# Buck-Boost_1.net
KiCad netlist of a schematic drawn in EasyEDA Pro
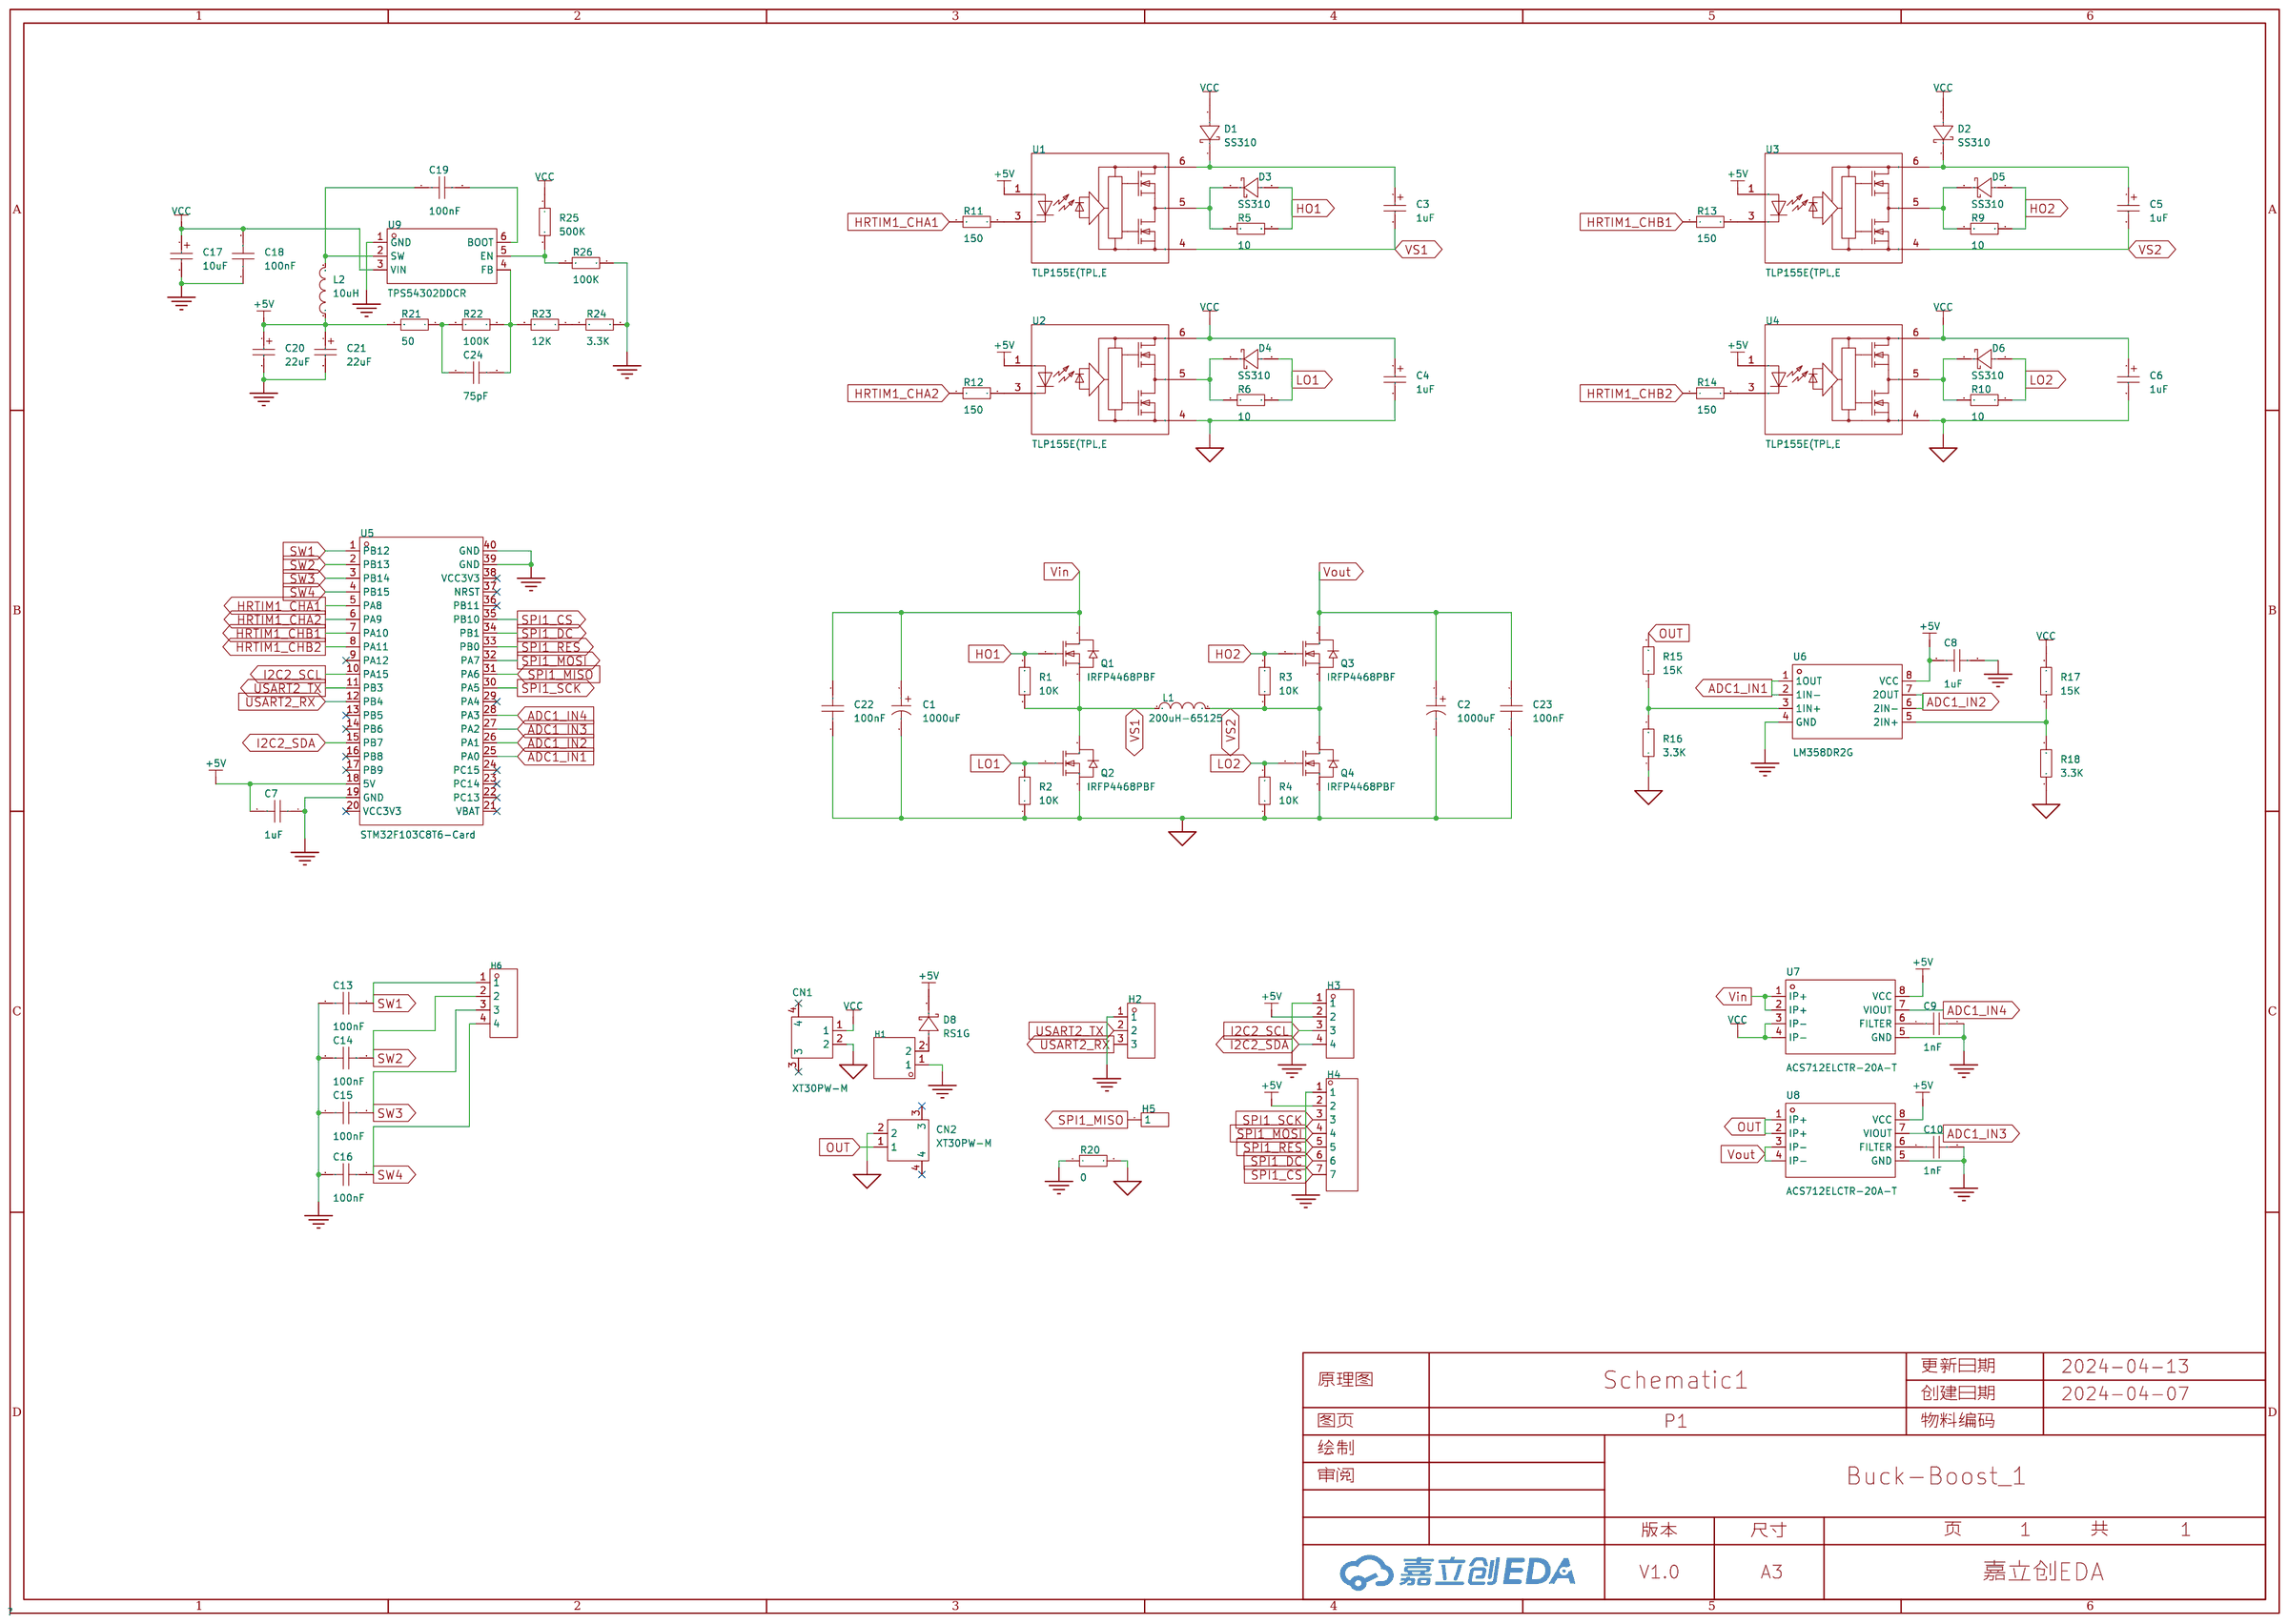
[diagram p0: schematic sheet]

(export (version "E")
  (design (tool "Eeschema 10.0.6"))
  (components
    (comp (ref "C1")
      (value "1000uF")
      (footprint "easyedapro:CAP-TH_BD16.0-P7.50-D1.5-FD")
      (description "容值:470uF;精度:±20%;额定电压:120V;纹波电流:-;等效串联电阻:-;")
      (fields (field (name "Manufacturer Part") "KF102M050I250A") (field (name "Manufacturer") "CapXon(丰宾)"))
      (libsource (lib "easyedapro") (part "ERS2BM471L35OT"))
    )
    (comp (ref "C2")
      (value "1000uF")
      (footprint "easyedapro:CAP-TH_BD16.0-P7.50-D1.5-FD")
      (description "容值:470uF;精度:±20%;额定电压:120V;纹波电流:-;等效串联电阻:-;")
      (fields (field (name "Manufacturer Part") "KF102M050I250A") (field (name "Manufacturer") "CapXon(丰宾)"))
      (libsource (lib "easyedapro") (part "ERS2BM471L35OT"))
    )
    (comp (ref "C3")
      (value "1uF")
      (footprint "easyedapro:CASE-A_3216")
      (description "容值:1uF;精度:±10%;额定电压:35V;等效串联电阻:7.5Ω@100kHz;")
      (fields (field (name "Manufacturer Part") "TAJA105K035RNJ") (field (name "Manufacturer") "Kyocera AVX"))
      (libsource (lib "easyedapro") (part "TAJA105K035RNJ"))
    )
    (comp (ref "C4")
      (value "1uF")
      (footprint "easyedapro:CASE-A_3216")
      (description "容值:1uF;精度:±10%;额定电压:35V;等效串联电阻:7.5Ω@100kHz;")
      (fields (field (name "Manufacturer Part") "TAJA105K035RNJ") (field (name "Manufacturer") "Kyocera AVX"))
      (libsource (lib "easyedapro") (part "TAJA105K035RNJ"))
    )
    (comp (ref "C5")
      (value "1uF")
      (footprint "easyedapro:CASE-A_3216")
      (description "容值:1uF;精度:±10%;额定电压:35V;等效串联电阻:7.5Ω@100kHz;")
      (fields (field (name "Manufacturer Part") "TAJA105K035RNJ") (field (name "Manufacturer") "Kyocera AVX"))
      (libsource (lib "easyedapro") (part "TAJA105K035RNJ"))
    )
    (comp (ref "C6")
      (value "1uF")
      (footprint "easyedapro:CASE-A_3216")
      (description "容值:1uF;精度:±10%;额定电压:35V;等效串联电阻:7.5Ω@100kHz;")
      (fields (field (name "Manufacturer Part") "TAJA105K035RNJ") (field (name "Manufacturer") "Kyocera AVX"))
      (libsource (lib "easyedapro") (part "TAJA105K035RNJ"))
    )
    (comp (ref "C7")
      (value "1uF")
      (footprint "easyedapro:C0805")
      (libsource (lib "easyedapro") (part "CapAcitance"))
    )
    (comp (ref "C8")
      (value "1uF")
      (footprint "easyedapro:C0805")
      (libsource (lib "easyedapro") (part "CapAcitance"))
    )
    (comp (ref "C9")
      (value "1nF")
      (footprint "easyedapro:C0805")
      (libsource (lib "easyedapro") (part "CapAcitance"))
    )
    (comp (ref "C10")
      (value "1nF")
      (footprint "easyedapro:C0805")
      (libsource (lib "easyedapro") (part "CapAcitance"))
    )
    (comp (ref "C13")
      (value "100nF")
      (footprint "easyedapro:C0805")
      (libsource (lib "easyedapro") (part "CapAcitance"))
    )
    (comp (ref "C14")
      (value "100nF")
      (footprint "easyedapro:C0805")
      (libsource (lib "easyedapro") (part "CapAcitance"))
    )
    (comp (ref "C15")
      (value "100nF")
      (footprint "easyedapro:C0805")
      (libsource (lib "easyedapro") (part "CapAcitance"))
    )
    (comp (ref "C16")
      (value "100nF")
      (footprint "easyedapro:C0805")
      (libsource (lib "easyedapro") (part "CapAcitance"))
    )
    (comp (ref "C17")
      (value "10uF")
      (footprint "easyedapro:CAP-SMD_L3.5-W2.8-R-RD")
      (description "容值:10uF;精度:±10%;额定电压:25V;等效串联电阻:2.5Ω@100kHz;")
      (fields (field (name "Manufacturer Part") "TAJB106K025RNJ") (field (name "Manufacturer") "Kyocera AVX"))
      (libsource (lib "easyedapro") (part "TAJB106K025RNJ"))
    )
    (comp (ref "C18")
      (value "100nF")
      (footprint "easyedapro:C0805")
      (libsource (lib "easyedapro") (part "CapAcitance"))
    )
    (comp (ref "C19")
      (value "100nF")
      (footprint "easyedapro:C0805")
      (libsource (lib "easyedapro") (part "CapAcitance"))
    )
    (comp (ref "C20")
      (value "22uF")
      (footprint "easyedapro:CASE-B_3528")
      (description "容值:22uF;精度:±10%;额定电压:16V;等效串联电阻:2.3Ω@100kHz;")
      (fields (field (name "Manufacturer Part") "TAJB226K016RNJ") (field (name "Manufacturer") "Kyocera AVX"))
      (libsource (lib "easyedapro") (part "TAJB226K016RNJ"))
    )
    (comp (ref "C21")
      (value "22uF")
      (footprint "easyedapro:CASE-B_3528")
      (description "容值:22uF;精度:±10%;额定电压:16V;等效串联电阻:2.3Ω@100kHz;")
      (fields (field (name "Manufacturer Part") "TAJB226K016RNJ") (field (name "Manufacturer") "Kyocera AVX"))
      (libsource (lib "easyedapro") (part "TAJB226K016RNJ"))
    )
    (comp (ref "C22")
      (value "100nF")
      (footprint "easyedapro:C0805")
      (libsource (lib "easyedapro") (part "CapAcitance"))
    )
    (comp (ref "C23")
      (value "100nF")
      (footprint "easyedapro:C0805")
      (libsource (lib "easyedapro") (part "CapAcitance"))
    )
    (comp (ref "C24")
      (value "75pF")
      (footprint "easyedapro:C0805")
      (libsource (lib "easyedapro") (part "CapAcitance"))
    )
    (comp (ref "CN1")
      (value "XT30PW-M")
      (footprint "easyedapro:CONN-TH_XT30PW-M")
      (description "类别:-;类型1:-;")
      (fields (field (name "Manufacturer") "AMASS(艾迈斯)"))
      (libsource (lib "easyedapro") (part "XT30PW-M"))
    )
    (comp (ref "CN2")
      (value "XT30PW-M")
      (footprint "easyedapro:CONN-TH_XT30PW-M")
      (description "类别:-;类型1:-;")
      (fields (field (name "Manufacturer") "AMASS(艾迈斯)"))
      (libsource (lib "easyedapro") (part "XT30PW-M"))
    )
    (comp (ref "D1")
      (value "SS310")
      (footprint "easyedapro:SMC_L6.9-W5.9-LS7.9-RD")
      (fields (field (name "Manufacturer") "MDD"))
      (libsource (lib "easyedapro") (part "SS56_C5161914"))
    )
    (comp (ref "D2")
      (value "SS310")
      (footprint "easyedapro:SMC_L6.9-W5.9-LS7.9-RD")
      (fields (field (name "Manufacturer") "MDD"))
      (libsource (lib "easyedapro") (part "SS56_C5161914"))
    )
    (comp (ref "D3")
      (value "SS310")
      (footprint "easyedapro:SMC_L6.9-W5.9-LS7.9-RD")
      (fields (field (name "Manufacturer") "MDD"))
      (libsource (lib "easyedapro") (part "SS56_C5161914"))
    )
    (comp (ref "D4")
      (value "SS310")
      (footprint "easyedapro:SMC_L6.9-W5.9-LS7.9-RD")
      (fields (field (name "Manufacturer") "MDD"))
      (libsource (lib "easyedapro") (part "SS56_C5161914"))
    )
    (comp (ref "D5")
      (value "SS310")
      (footprint "easyedapro:SMC_L6.9-W5.9-LS7.9-RD")
      (fields (field (name "Manufacturer") "MDD"))
      (libsource (lib "easyedapro") (part "SS56_C5161914"))
    )
    (comp (ref "D6")
      (value "SS310")
      (footprint "easyedapro:SMC_L6.9-W5.9-LS7.9-RD")
      (fields (field (name "Manufacturer") "MDD"))
      (libsource (lib "easyedapro") (part "SS56_C5161914"))
    )
    (comp (ref "D8")
      (value "RS1G")
      (footprint "easyedapro:SMC_L6.9-W5.9-LS7.9-RD")
      (fields (field (name "Manufacturer") "宏迦橙"))
      (libsource (lib "easyedapro") (part "SS56_C5161914"))
    )
    (comp (ref "H1")
      (value "~")
      (footprint "easyedapro:HDR-TH_2P-P2.54-V-M-1")
      (libsource (lib "easyedapro") (part "210S-1*2P L=11.6MMGold-plated black"))
    )
    (comp (ref "H2")
      (value "~")
      (footprint "easyedapro:HDR-TH_3P-P2.54-V-M")
      (libsource (lib "easyedapro") (part "PZ254V-11-03P_C2937625"))
    )
    (comp (ref "H3")
      (value "~")
      (footprint "easyedapro:HDR-TH_4P-P2.54-V-F")
      (libsource (lib "easyedapro") (part "2.54-1*4P母"))
    )
    (comp (ref "H4")
      (value "~")
      (footprint "easyedapro:HDR-TH_7P-P2.54-V-F")
      (libsource (lib "easyedapro") (part "220S-1*7P H=8.5MM Ytype Gold-plated"))
    )
    (comp (ref "H5")
      (value "~")
      (footprint "easyedapro:HDR-TH_1P-V-M_XKB_X4611WV-01I-C28D40")
      (libsource (lib "easyedapro") (part "HDR_1x1"))
    )
    (comp (ref "H6")
      (value "~")
      (footprint "easyedapro:HDR-TH_4P-P2.54-V-M")
      (libsource (lib "easyedapro") (part "PZ254V-11-04P"))
    )
    (comp (ref "L1")
      (value "200uH-65125")
      (footprint "easyedapro:IND-TH_200UH-65125")
      (libsource (lib "easyedapro") (part "200UH-65125"))
    )
    (comp (ref "L2")
      (value "10uH")
      (footprint "easyedapro:IND-SMD_L7.3-W6.8")
      (description "电感值:10uH;精度:±20%;额定电流:4.5A;饱和电流(Isat):5.5A;类型:一体成型电感;")
      (fields (field (name "Manufacturer Part") "FXL0420-100-M") (field (name "Manufacturer") "cjiang(长江微电)"))
      (libsource (lib "easyedapro") (part "FXL0630-100-M"))
    )
    (comp (ref "Q1")
      (value "IRFP4468PBF")
      (footprint "easyedapro:TO-247AC-3_L15.8-W5.0-P5.46-L")
      (fields (field (name "Manufacturer") "Infineon(英飞凌)"))
      (libsource (lib "easyedapro") (part "IRFP4468PBF"))
    )
    (comp (ref "Q2")
      (value "IRFP4468PBF")
      (footprint "easyedapro:TO-247AC-3_L15.8-W5.0-P5.46-L")
      (fields (field (name "Manufacturer") "Infineon(英飞凌)"))
      (libsource (lib "easyedapro") (part "IRFP4468PBF"))
    )
    (comp (ref "Q3")
      (value "IRFP4468PBF")
      (footprint "easyedapro:TO-247AC-3_L15.8-W5.0-P5.46-L")
      (fields (field (name "Manufacturer") "Infineon(英飞凌)"))
      (libsource (lib "easyedapro") (part "IRFP4468PBF"))
    )
    (comp (ref "Q4")
      (value "IRFP4468PBF")
      (footprint "easyedapro:TO-247AC-3_L15.8-W5.0-P5.46-L")
      (fields (field (name "Manufacturer") "Infineon(英飞凌)"))
      (libsource (lib "easyedapro") (part "IRFP4468PBF"))
    )
    (comp (ref "R1") (value "10K") (footprint "easyedapro:R0805") (libsource (lib "easyedapro") (part "电阻")))
    (comp (ref "R2") (value "10K") (footprint "easyedapro:R0805") (libsource (lib "easyedapro") (part "电阻")))
    (comp (ref "R3") (value "10K") (footprint "easyedapro:R0805") (libsource (lib "easyedapro") (part "电阻")))
    (comp (ref "R4") (value "10K") (footprint "easyedapro:R0805") (libsource (lib "easyedapro") (part "电阻")))
    (comp (ref "R5") (value "10") (footprint "easyedapro:R0805") (libsource (lib "easyedapro") (part "电阻")))
    (comp (ref "R6") (value "10") (footprint "easyedapro:R0805") (libsource (lib "easyedapro") (part "电阻")))
    (comp (ref "R9") (value "10") (footprint "easyedapro:R0805") (libsource (lib "easyedapro") (part "电阻")))
    (comp (ref "R10") (value "10") (footprint "easyedapro:R0805") (libsource (lib "easyedapro") (part "电阻")))
    (comp (ref "R11") (value "150") (footprint "easyedapro:R0805") (libsource (lib "easyedapro") (part "电阻")))
    (comp (ref "R12") (value "150") (footprint "easyedapro:R0805") (libsource (lib "easyedapro") (part "电阻")))
    (comp (ref "R13") (value "150") (footprint "easyedapro:R0805") (libsource (lib "easyedapro") (part "电阻")))
    (comp (ref "R14") (value "150") (footprint "easyedapro:R0805") (libsource (lib "easyedapro") (part "电阻")))
    (comp (ref "R15") (value "15K") (footprint "easyedapro:R0805") (libsource (lib "easyedapro") (part "电阻")))
    (comp (ref "R16")
      (value "3.3K")
      (footprint "easyedapro:R0805")
      (libsource (lib "easyedapro") (part "电阻"))
    )
    (comp (ref "R17") (value "15K") (footprint "easyedapro:R0805") (libsource (lib "easyedapro") (part "电阻")))
    (comp (ref "R18")
      (value "3.3K")
      (footprint "easyedapro:R0805")
      (libsource (lib "easyedapro") (part "电阻"))
    )
    (comp (ref "R20") (value "0") (footprint "easyedapro:R0805") (libsource (lib "easyedapro") (part "电阻")))
    (comp (ref "R21") (value "50") (footprint "easyedapro:R0805") (libsource (lib "easyedapro") (part "电阻")))
    (comp (ref "R22")
      (value "100K")
      (footprint "easyedapro:R0805")
      (libsource (lib "easyedapro") (part "电阻"))
    )
    (comp (ref "R23") (value "12K") (footprint "easyedapro:R0805") (libsource (lib "easyedapro") (part "电阻")))
    (comp (ref "R24")
      (value "3.3K")
      (footprint "easyedapro:R0805")
      (libsource (lib "easyedapro") (part "电阻"))
    )
    (comp (ref "R25")
      (value "500K")
      (footprint "easyedapro:R0805")
      (libsource (lib "easyedapro") (part "电阻"))
    )
    (comp (ref "R26")
      (value "100K")
      (footprint "easyedapro:R0805")
      (libsource (lib "easyedapro") (part "电阻"))
    )
    (comp (ref "U1")
      (value "TLP155E(TPL,E")
      (footprint "easyedapro:OPTO-SMD-5_L3.7-W4.6-P1.27-LS7.0-BR")
      (description "输入类型:DC;电源电压:10V~30V;共模瞬变抗扰度CMTI:15kV/us;传播延迟tpLH/tpHL:170ns；170ns;")
      (fields (field (name "Manufacturer") "TOSHIBA(东芝)"))
      (libsource (lib "easyedapro") (part "TLP155E(TPL,E"))
    )
    (comp (ref "U2")
      (value "TLP155E(TPL,E")
      (footprint "easyedapro:OPTO-SMD-5_L3.7-W4.6-P1.27-LS7.0-BR")
      (description "输入类型:DC;电源电压:10V~30V;共模瞬变抗扰度CMTI:15kV/us;传播延迟tpLH/tpHL:170ns；170ns;")
      (fields (field (name "Manufacturer") "TOSHIBA(东芝)"))
      (libsource (lib "easyedapro") (part "TLP155E(TPL,E"))
    )
    (comp (ref "U3")
      (value "TLP155E(TPL,E")
      (footprint "easyedapro:OPTO-SMD-5_L3.7-W4.6-P1.27-LS7.0-BR")
      (description "输入类型:DC;电源电压:10V~30V;共模瞬变抗扰度CMTI:15kV/us;传播延迟tpLH/tpHL:170ns；170ns;")
      (fields (field (name "Manufacturer") "TOSHIBA(东芝)"))
      (libsource (lib "easyedapro") (part "TLP155E(TPL,E"))
    )
    (comp (ref "U4")
      (value "TLP155E(TPL,E")
      (footprint "easyedapro:OPTO-SMD-5_L3.7-W4.6-P1.27-LS7.0-BR")
      (description "输入类型:DC;电源电压:10V~30V;共模瞬变抗扰度CMTI:15kV/us;传播延迟tpLH/tpHL:170ns；170ns;")
      (fields (field (name "Manufacturer") "TOSHIBA(东芝)"))
      (libsource (lib "easyedapro") (part "TLP155E(TPL,E"))
    )
    (comp (ref "U5")
      (value "STM32F103C8T6-Card")
      (footprint "easyedapro:CONN-TH_L53.3-W22.9_STM32F103C8T6-CARD")
      (libsource (lib "easyedapro") (part "STM32F103C8T6-CARD"))
    )
    (comp (ref "U6")
      (value "LM358DR2G")
      (footprint "easyedapro:SOIC-8_L5.0-W4.0-P1.27-LS6.0-BL")
      (description "放大器数:双路;增益带宽积(GBP):1MHz;输入偏置电流(Ib):45nA;压摆率(SR):-;带宽(-3db):-;")
      (fields (field (name "Manufacturer") "onsemi(安森美)"))
      (libsource (lib "easyedapro") (part "LM358DR2G"))
    )
    (comp (ref "U7")
      (value "ACS712ELCTR-20A-T")
      (footprint "easyedapro:SOIC-8_L4.9-W3.9-P1.27-LS6.0-BL")
      (description "电流测量范围:20A;灵敏度:100mV/A;")
      (fields (field (name "Manufacturer") "ALLEGRO(美国埃戈罗)"))
      (libsource (lib "easyedapro") (part "ACS712ELCTR-20A-T"))
    )
    (comp (ref "U8")
      (value "ACS712ELCTR-20A-T")
      (footprint "easyedapro:SOIC-8_L4.9-W3.9-P1.27-LS6.0-BL")
      (description "电流测量范围:20A;灵敏度:100mV/A;")
      (fields (field (name "Manufacturer") "ALLEGRO(美国埃戈罗)"))
      (libsource (lib "easyedapro") (part "ACS712ELCTR-20A-T"))
    )
    (comp (ref "U9")
      (value "TPS54302DDCR")
      (footprint "easyedapro:SOT-23-6_L2.9-W1.6-P0.95-LS2.8-BL")
      (description "功能类型:降压型;输出类型:可调;输入电压:4.5V~28V;输出电压:596mV~28V;输出电流(最大值):3A;")
      (fields (field (name "Manufacturer") "TI(德州仪器)"))
      (libsource (lib "easyedapro") (part "TPS54302DDCR_C311983"))
    )
  )
  (nets
    (net (code "1") (name "+5V") (class "Default")
      (node (ref "C20") (pin "1") (pinfunction "1_1") (pintype "input"))
      (node (ref "C21") (pin "1") (pinfunction "1_1") (pintype "input"))
      (node (ref "C7") (pin "2") (pinfunction "2_2") (pintype "input"))
      (node (ref "C8") (pin "1") (pinfunction "1_1") (pintype "input"))
      (node (ref "D8") (pin "1") (pinfunction "K_1") (pintype "unspecified"))
      (node (ref "H3") (pin "2") (pinfunction "2_2") (pintype "unspecified"))
      (node (ref "H4") (pin "2") (pinfunction "2_2") (pintype "unspecified"))
      (node (ref "L2") (pin "1") (pinfunction "1_1") (pintype "unspecified"))
      (node (ref "R21") (pin "2") (pinfunction "2_2") (pintype "input"))
      (node (ref "U1") (pin "1") (pinfunction "AN_1") (pintype "unspecified"))
      (node (ref "U2") (pin "1") (pinfunction "AN_1") (pintype "unspecified"))
      (node (ref "U3") (pin "1") (pinfunction "AN_1") (pintype "unspecified"))
      (node (ref "U4") (pin "1") (pinfunction "AN_1") (pintype "unspecified"))
      (node (ref "U5") (pin "18") (pinfunction "5V_18") (pintype "unspecified"))
      (node (ref "U6") (pin "8") (pinfunction "VCC_8") (pintype "unspecified"))
      (node (ref "U7") (pin "8") (pinfunction "VCC_8") (pintype "unspecified"))
      (node (ref "U8") (pin "8") (pinfunction "VCC_8") (pintype "unspecified"))
    )
    (net (code "2") (name "ADC1_IN1") (class "Default")
      (node (ref "U5") (pin "25") (pinfunction "PA0_25") (pintype "unspecified"))
      (node (ref "U6") (pin "1") (pinfunction "1OUT_1") (pintype "unspecified"))
      (node (ref "U6") (pin "2") (pinfunction "1IN-_2") (pintype "unspecified"))
    )
    (net (code "3") (name "ADC1_IN2") (class "Default")
      (node (ref "U5") (pin "26") (pinfunction "PA1_26") (pintype "unspecified"))
      (node (ref "U6") (pin "6") (pinfunction "2IN-_6") (pintype "unspecified"))
      (node (ref "U6") (pin "7") (pinfunction "2OUT_7") (pintype "unspecified"))
    )
    (net (code "4") (name "ADC1_IN3") (class "Default")
      (node (ref "U5") (pin "27") (pinfunction "PA2_27") (pintype "unspecified"))
      (node (ref "U8") (pin "7") (pinfunction "VIOUT_7") (pintype "unspecified"))
    )
    (net (code "5") (name "ADC1_IN4") (class "Default")
      (node (ref "U5") (pin "28") (pinfunction "PA3_28") (pintype "unspecified"))
      (node (ref "U7") (pin "7") (pinfunction "VIOUT_7") (pintype "unspecified"))
    )
    (net (code "6") (name "AGND") (class "Default")
      (node (ref "C1") (pin "2") (pinfunction "2_2") (pintype "input"))
      (node (ref "C2") (pin "2") (pinfunction "2_2") (pintype "input"))
      (node (ref "C22") (pin "2") (pinfunction "2_2") (pintype "input"))
      (node (ref "C23") (pin "2") (pinfunction "2_2") (pintype "input"))
      (node (ref "C4") (pin "2") (pinfunction "2_2") (pintype "input"))
      (node (ref "C6") (pin "2") (pinfunction "2_2") (pintype "input"))
      (node (ref "CN1") (pin "2") (pinfunction "2_2") (pintype "unspecified"))
      (node (ref "CN2") (pin "2") (pinfunction "2_2") (pintype "unspecified"))
      (node (ref "Q2") (pin "3") (pinfunction "S_3") (pintype "unspecified"))
      (node (ref "Q4") (pin "3") (pinfunction "S_3") (pintype "unspecified"))
      (node (ref "R16") (pin "1") (pinfunction "1_1") (pintype "input"))
      (node (ref "R18") (pin "1") (pinfunction "1_1") (pintype "input"))
      (node (ref "R2") (pin "1") (pinfunction "1_1") (pintype "input"))
      (node (ref "R20") (pin "2") (pinfunction "2_2") (pintype "input"))
      (node (ref "R4") (pin "1") (pinfunction "1_1") (pintype "input"))
      (node (ref "U2") (pin "4") (pinfunction "GND_4") (pintype "unspecified"))
      (node (ref "U4") (pin "4") (pinfunction "GND_4") (pintype "unspecified"))
    )
    (net (code "7") (name "GND") (class "Default")
      (node (ref "C10") (pin "2") (pinfunction "2_2") (pintype "input"))
      (node (ref "C13") (pin "1") (pinfunction "1_1") (pintype "input"))
      (node (ref "C14") (pin "1") (pinfunction "1_1") (pintype "input"))
      (node (ref "C15") (pin "1") (pinfunction "1_1") (pintype "input"))
      (node (ref "C16") (pin "1") (pinfunction "1_1") (pintype "input"))
      (node (ref "C17") (pin "2") (pinfunction "2_2") (pintype "input"))
      (node (ref "C18") (pin "1") (pinfunction "1_1") (pintype "input"))
      (node (ref "C20") (pin "2") (pinfunction "2_2") (pintype "input"))
      (node (ref "C21") (pin "2") (pinfunction "2_2") (pintype "input"))
      (node (ref "C7") (pin "1") (pinfunction "1_1") (pintype "input"))
      (node (ref "C8") (pin "2") (pinfunction "2_2") (pintype "input"))
      (node (ref "C9") (pin "2") (pinfunction "2_2") (pintype "input"))
      (node (ref "H1") (pin "1") (pinfunction "1_1") (pintype "input"))
      (node (ref "H2") (pin "1") (pinfunction "1_1") (pintype "input"))
      (node (ref "H3") (pin "1") (pinfunction "1_1") (pintype "unspecified"))
      (node (ref "H4") (pin "1") (pinfunction "1_1") (pintype "unspecified"))
      (node (ref "R20") (pin "1") (pinfunction "1_1") (pintype "input"))
      (node (ref "R24") (pin "2") (pinfunction "2_2") (pintype "input"))
      (node (ref "R26") (pin "2") (pinfunction "2_2") (pintype "input"))
      (node (ref "U5") (pin "19") (pinfunction "GND_19") (pintype "unspecified"))
      (node (ref "U5") (pin "39") (pinfunction "GND_39") (pintype "unspecified"))
      (node (ref "U5") (pin "40") (pinfunction "GND_40") (pintype "unspecified"))
      (node (ref "U6") (pin "4") (pinfunction "GND_4") (pintype "unspecified"))
      (node (ref "U7") (pin "5") (pinfunction "GND_5") (pintype "unspecified"))
      (node (ref "U8") (pin "5") (pinfunction "GND_5") (pintype "unspecified"))
      (node (ref "U9") (pin "1") (pinfunction "GND_1") (pintype "unspecified"))
    )
    (net (code "8") (name "HO1") (class "Default")
      (node (ref "D3") (pin "2") (pinfunction "A_2") (pintype "unspecified"))
      (node (ref "Q1") (pin "1") (pinfunction "G_1") (pintype "unspecified"))
      (node (ref "R1") (pin "2") (pinfunction "2_2") (pintype "input"))
      (node (ref "R5") (pin "2") (pinfunction "2_2") (pintype "input"))
    )
    (net (code "9") (name "HO2") (class "Default")
      (node (ref "D5") (pin "2") (pinfunction "A_2") (pintype "unspecified"))
      (node (ref "Q3") (pin "1") (pinfunction "G_1") (pintype "unspecified"))
      (node (ref "R3") (pin "2") (pinfunction "2_2") (pintype "input"))
      (node (ref "R9") (pin "2") (pinfunction "2_2") (pintype "input"))
    )
    (net (code "10") (name "HRTIM1_CHA1") (class "Default")
      (node (ref "R11") (pin "1") (pinfunction "1_1") (pintype "input"))
      (node (ref "U5") (pin "5") (pinfunction "PA8_5") (pintype "unspecified"))
    )
    (net (code "11") (name "HRTIM1_CHA2") (class "Default")
      (node (ref "R12") (pin "1") (pinfunction "1_1") (pintype "input"))
      (node (ref "U5") (pin "6") (pinfunction "PA9_6") (pintype "unspecified"))
    )
    (net (code "12") (name "HRTIM1_CHB1") (class "Default")
      (node (ref "R13") (pin "1") (pinfunction "1_1") (pintype "input"))
      (node (ref "U5") (pin "7") (pinfunction "PA10_7") (pintype "unspecified"))
    )
    (net (code "13") (name "HRTIM1_CHB2") (class "Default")
      (node (ref "R14") (pin "1") (pinfunction "1_1") (pintype "input"))
      (node (ref "U5") (pin "8") (pinfunction "PA11_8") (pintype "unspecified"))
    )
    (net (code "14") (name "I2C2_SCL") (class "Default")
      (node (ref "H3") (pin "3") (pinfunction "3_3") (pintype "unspecified"))
      (node (ref "U5") (pin "10") (pinfunction "PA15_10") (pintype "unspecified"))
    )
    (net (code "15") (name "I2C2_SDA") (class "Default")
      (node (ref "H3") (pin "4") (pinfunction "4_4") (pintype "unspecified"))
      (node (ref "U5") (pin "15") (pinfunction "PB7_15") (pintype "unspecified"))
    )
    (net (code "16") (name "LO1") (class "Default")
      (node (ref "D4") (pin "2") (pinfunction "A_2") (pintype "unspecified"))
      (node (ref "Q2") (pin "1") (pinfunction "G_1") (pintype "unspecified"))
      (node (ref "R2") (pin "2") (pinfunction "2_2") (pintype "input"))
      (node (ref "R6") (pin "2") (pinfunction "2_2") (pintype "input"))
    )
    (net (code "17") (name "LO2") (class "Default")
      (node (ref "D6") (pin "2") (pinfunction "A_2") (pintype "unspecified"))
      (node (ref "Q4") (pin "1") (pinfunction "G_1") (pintype "unspecified"))
      (node (ref "R10") (pin "2") (pinfunction "2_2") (pintype "input"))
      (node (ref "R4") (pin "2") (pinfunction "2_2") (pintype "input"))
    )
    (net (code "18") (name "Net-(C24-Pad1)") (class "Default")
      (node (ref "C24") (pin "1") (pinfunction "1_1") (pintype "input"))
      (node (ref "R21") (pin "1") (pinfunction "1_1") (pintype "input"))
      (node (ref "R22") (pin "2") (pinfunction "2_2") (pintype "input"))
    )
    (net (code "19") (name "Net-(D1-K)") (class "Default")
      (node (ref "C3") (pin "1") (pinfunction "1_1") (pintype "input"))
      (node (ref "D1") (pin "1") (pinfunction "K_1") (pintype "unspecified"))
      (node (ref "U1") (pin "6") (pinfunction "VCC_6") (pintype "unspecified"))
    )
    (net (code "20") (name "Net-(D2-K)") (class "Default")
      (node (ref "C5") (pin "1") (pinfunction "1_1") (pintype "input"))
      (node (ref "D2") (pin "1") (pinfunction "K_1") (pintype "unspecified"))
      (node (ref "U3") (pin "6") (pinfunction "VCC_6") (pintype "unspecified"))
    )
    (net (code "21") (name "Net-(D3-K)") (class "Default")
      (node (ref "D3") (pin "1") (pinfunction "K_1") (pintype "unspecified"))
      (node (ref "R5") (pin "1") (pinfunction "1_1") (pintype "input"))
      (node (ref "U1") (pin "5") (pinfunction "VO_5") (pintype "unspecified"))
    )
    (net (code "22") (name "Net-(D4-K)") (class "Default")
      (node (ref "D4") (pin "1") (pinfunction "K_1") (pintype "unspecified"))
      (node (ref "R6") (pin "1") (pinfunction "1_1") (pintype "input"))
      (node (ref "U2") (pin "5") (pinfunction "VO_5") (pintype "unspecified"))
    )
    (net (code "23") (name "Net-(D5-K)") (class "Default")
      (node (ref "D5") (pin "1") (pinfunction "K_1") (pintype "unspecified"))
      (node (ref "R9") (pin "1") (pinfunction "1_1") (pintype "input"))
      (node (ref "U3") (pin "5") (pinfunction "VO_5") (pintype "unspecified"))
    )
    (net (code "24") (name "Net-(D6-K)") (class "Default")
      (node (ref "D6") (pin "1") (pinfunction "K_1") (pintype "unspecified"))
      (node (ref "R10") (pin "1") (pinfunction "1_1") (pintype "input"))
      (node (ref "U4") (pin "5") (pinfunction "VO_5") (pintype "unspecified"))
    )
    (net (code "25") (name "Net-(D8-A)") (class "Default")
      (node (ref "D8") (pin "2") (pinfunction "A_2") (pintype "unspecified"))
      (node (ref "H1") (pin "2") (pinfunction "2_2") (pintype "input"))
    )
    (net (code "26") (name "Net-(R23-Pad1)") (class "Default")
      (node (ref "R23") (pin "1") (pinfunction "1_1") (pintype "input"))
      (node (ref "R24") (pin "1") (pinfunction "1_1") (pintype "input"))
    )
    (net (code "27") (name "Net-(U1-CAT)") (class "Default")
      (node (ref "R11") (pin "2") (pinfunction "2_2") (pintype "input"))
      (node (ref "U1") (pin "3") (pinfunction "CAT_3") (pintype "unspecified"))
    )
    (net (code "28") (name "Net-(U2-CAT)") (class "Default")
      (node (ref "R12") (pin "2") (pinfunction "2_2") (pintype "input"))
      (node (ref "U2") (pin "3") (pinfunction "CAT_3") (pintype "unspecified"))
    )
    (net (code "29") (name "Net-(U3-CAT)") (class "Default")
      (node (ref "R13") (pin "2") (pinfunction "2_2") (pintype "input"))
      (node (ref "U3") (pin "3") (pinfunction "CAT_3") (pintype "unspecified"))
    )
    (net (code "30") (name "Net-(U4-CAT)") (class "Default")
      (node (ref "R14") (pin "2") (pinfunction "2_2") (pintype "input"))
      (node (ref "U4") (pin "3") (pinfunction "CAT_3") (pintype "unspecified"))
    )
    (net (code "31") (name "Net-(U6-1IN+)") (class "Default")
      (node (ref "R15") (pin "1") (pinfunction "1_1") (pintype "input"))
      (node (ref "R16") (pin "2") (pinfunction "2_2") (pintype "input"))
      (node (ref "U6") (pin "3") (pinfunction "1IN+_3") (pintype "unspecified"))
    )
    (net (code "32") (name "Net-(U6-2IN+)") (class "Default")
      (node (ref "R17") (pin "1") (pinfunction "1_1") (pintype "input"))
      (node (ref "R18") (pin "2") (pinfunction "2_2") (pintype "input"))
      (node (ref "U6") (pin "5") (pinfunction "2IN+_5") (pintype "unspecified"))
    )
    (net (code "33") (name "Net-(U7-FILTER)") (class "Default")
      (node (ref "C9") (pin "1") (pinfunction "1_1") (pintype "input"))
      (node (ref "U7") (pin "6") (pinfunction "FILTER_6") (pintype "unspecified"))
    )
    (net (code "34") (name "Net-(U8-FILTER)") (class "Default")
      (node (ref "C10") (pin "1") (pinfunction "1_1") (pintype "input"))
      (node (ref "U8") (pin "6") (pinfunction "FILTER_6") (pintype "unspecified"))
    )
    (net (code "35") (name "Net-(U9-BOOT)") (class "Default")
      (node (ref "C19") (pin "2") (pinfunction "2_2") (pintype "input"))
      (node (ref "U9") (pin "6") (pinfunction "BOOT_6") (pintype "unspecified"))
    )
    (net (code "36") (name "Net-(U9-EN)") (class "Default")
      (node (ref "R25") (pin "2") (pinfunction "2_2") (pintype "input"))
      (node (ref "R26") (pin "1") (pinfunction "1_1") (pintype "input"))
      (node (ref "U9") (pin "5") (pinfunction "EN_5") (pintype "unspecified"))
    )
    (net (code "37") (name "Net-(U9-FB)") (class "Default")
      (node (ref "C24") (pin "2") (pinfunction "2_2") (pintype "input"))
      (node (ref "R22") (pin "1") (pinfunction "1_1") (pintype "input"))
      (node (ref "R23") (pin "2") (pinfunction "2_2") (pintype "input"))
      (node (ref "U9") (pin "4") (pinfunction "FB_4") (pintype "unspecified"))
    )
    (net (code "38") (name "Net-(U9-SW)") (class "Default")
      (node (ref "C19") (pin "1") (pinfunction "1_1") (pintype "input"))
      (node (ref "L2") (pin "2") (pinfunction "2_2") (pintype "unspecified"))
      (node (ref "U9") (pin "2") (pinfunction "SW_2") (pintype "unspecified"))
    )
    (net (code "39") (name "OUT") (class "Default")
      (node (ref "CN2") (pin "1") (pinfunction "1_1") (pintype "unspecified"))
      (node (ref "R15") (pin "2") (pinfunction "2_2") (pintype "input"))
      (node (ref "U8") (pin "1") (pinfunction "IP+_1") (pintype "unspecified"))
      (node (ref "U8") (pin "2") (pinfunction "IP+_2") (pintype "unspecified"))
    )
    (net (code "40") (name "SPI1_CS") (class "Default")
      (node (ref "H4") (pin "7") (pinfunction "7_7") (pintype "unspecified"))
      (node (ref "U5") (pin "35") (pinfunction "PB10_35") (pintype "unspecified"))
    )
    (net (code "41") (name "SPI1_DC") (class "Default")
      (node (ref "H4") (pin "6") (pinfunction "6_6") (pintype "unspecified"))
      (node (ref "U5") (pin "34") (pinfunction "PB1_34") (pintype "unspecified"))
    )
    (net (code "42") (name "SPI1_MISO") (class "Default")
      (node (ref "H5") (pin "1") (pinfunction "1_1") (pintype "unspecified"))
      (node (ref "U5") (pin "31") (pinfunction "PA6_31") (pintype "unspecified"))
    )
    (net (code "43") (name "SPI1_MOSI") (class "Default")
      (node (ref "H4") (pin "4") (pinfunction "4_4") (pintype "unspecified"))
      (node (ref "U5") (pin "32") (pinfunction "PA7_32") (pintype "unspecified"))
    )
    (net (code "44") (name "SPI1_RES") (class "Default")
      (node (ref "H4") (pin "5") (pinfunction "5_5") (pintype "unspecified"))
      (node (ref "U5") (pin "33") (pinfunction "PB0_33") (pintype "unspecified"))
    )
    (net (code "45") (name "SPI1_SCK") (class "Default")
      (node (ref "H4") (pin "3") (pinfunction "3_3") (pintype "unspecified"))
      (node (ref "U5") (pin "30") (pinfunction "PA5_30") (pintype "unspecified"))
    )
    (net (code "46") (name "SW1") (class "Default")
      (node (ref "C13") (pin "2") (pinfunction "2_2") (pintype "input"))
      (node (ref "H6") (pin "1") (pinfunction "1_1") (pintype "input"))
      (node (ref "U5") (pin "1") (pinfunction "PB12_1") (pintype "unspecified"))
    )
    (net (code "47") (name "SW2") (class "Default")
      (node (ref "C14") (pin "2") (pinfunction "2_2") (pintype "input"))
      (node (ref "H6") (pin "2") (pinfunction "2_2") (pintype "input"))
      (node (ref "U5") (pin "2") (pinfunction "PB13_2") (pintype "unspecified"))
    )
    (net (code "48") (name "SW3") (class "Default")
      (node (ref "C15") (pin "2") (pinfunction "2_2") (pintype "input"))
      (node (ref "H6") (pin "3") (pinfunction "3_3") (pintype "input"))
      (node (ref "U5") (pin "3") (pinfunction "PB14_3") (pintype "unspecified"))
    )
    (net (code "49") (name "SW4") (class "Default")
      (node (ref "C16") (pin "2") (pinfunction "2_2") (pintype "input"))
      (node (ref "H6") (pin "4") (pinfunction "4_4") (pintype "input"))
      (node (ref "U5") (pin "4") (pinfunction "PB15_4") (pintype "unspecified"))
    )
    (net (code "50") (name "USART2_RX") (class "Default")
      (node (ref "H2") (pin "3") (pinfunction "3_3") (pintype "input"))
      (node (ref "U5") (pin "12") (pinfunction "PB4_12") (pintype "unspecified"))
    )
    (net (code "51") (name "USART2_TX") (class "Default")
      (node (ref "H2") (pin "2") (pinfunction "2_2") (pintype "input"))
      (node (ref "U5") (pin "11") (pinfunction "PB3_11") (pintype "unspecified"))
    )
    (net (code "52") (name "VCC") (class "Default")
      (node (ref "C17") (pin "1") (pinfunction "1_1") (pintype "input"))
      (node (ref "C18") (pin "2") (pinfunction "2_2") (pintype "input"))
      (node (ref "C4") (pin "1") (pinfunction "1_1") (pintype "input"))
      (node (ref "C6") (pin "1") (pinfunction "1_1") (pintype "input"))
      (node (ref "CN1") (pin "1") (pinfunction "1_1") (pintype "unspecified"))
      (node (ref "D1") (pin "2") (pinfunction "A_2") (pintype "unspecified"))
      (node (ref "D2") (pin "2") (pinfunction "A_2") (pintype "unspecified"))
      (node (ref "R17") (pin "2") (pinfunction "2_2") (pintype "input"))
      (node (ref "R25") (pin "1") (pinfunction "1_1") (pintype "input"))
      (node (ref "U2") (pin "6") (pinfunction "VCC_6") (pintype "unspecified"))
      (node (ref "U4") (pin "6") (pinfunction "VCC_6") (pintype "unspecified"))
      (node (ref "U7") (pin "3") (pinfunction "IP-_3") (pintype "unspecified"))
      (node (ref "U7") (pin "4") (pinfunction "IP-_4") (pintype "unspecified"))
      (node (ref "U9") (pin "3") (pinfunction "VIN_3") (pintype "unspecified"))
    )
    (net (code "53") (name "VS1") (class "Default")
      (node (ref "C3") (pin "2") (pinfunction "2_2") (pintype "input"))
      (node (ref "L1") (pin "1") (pinfunction "1_1") (pintype "input"))
      (node (ref "Q1") (pin "3") (pinfunction "S_3") (pintype "unspecified"))
      (node (ref "Q2") (pin "2") (pinfunction "D_2") (pintype "unspecified"))
      (node (ref "R1") (pin "1") (pinfunction "1_1") (pintype "input"))
      (node (ref "U1") (pin "4") (pinfunction "GND_4") (pintype "unspecified"))
    )
    (net (code "54") (name "VS2") (class "Default")
      (node (ref "C5") (pin "2") (pinfunction "2_2") (pintype "input"))
      (node (ref "L1") (pin "2") (pinfunction "2_2") (pintype "input"))
      (node (ref "Q3") (pin "3") (pinfunction "S_3") (pintype "unspecified"))
      (node (ref "Q4") (pin "2") (pinfunction "D_2") (pintype "unspecified"))
      (node (ref "R3") (pin "1") (pinfunction "1_1") (pintype "input"))
      (node (ref "U3") (pin "4") (pinfunction "GND_4") (pintype "unspecified"))
    )
    (net (code "55") (name "Vin") (class "Default")
      (node (ref "C1") (pin "1") (pinfunction "1_1") (pintype "input"))
      (node (ref "C22") (pin "1") (pinfunction "1_1") (pintype "input"))
      (node (ref "Q1") (pin "2") (pinfunction "D_2") (pintype "unspecified"))
      (node (ref "U7") (pin "1") (pinfunction "IP+_1") (pintype "unspecified"))
      (node (ref "U7") (pin "2") (pinfunction "IP+_2") (pintype "unspecified"))
    )
    (net (code "56") (name "Vout") (class "Default")
      (node (ref "C2") (pin "1") (pinfunction "1_1") (pintype "input"))
      (node (ref "C23") (pin "1") (pinfunction "1_1") (pintype "input"))
      (node (ref "Q3") (pin "2") (pinfunction "D_2") (pintype "unspecified"))
      (node (ref "U8") (pin "3") (pinfunction "IP-_3") (pintype "unspecified"))
      (node (ref "U8") (pin "4") (pinfunction "IP-_4") (pintype "unspecified"))
    )
    (net (code "57") (name "unconnected-(CN1-Pad3)") (class "Default")
      (node (ref "CN1") (pin "3") (pinfunction "3_3") (pintype "unspecified+no_connect"))
    )
    (net (code "58") (name "unconnected-(CN1-Pad4)") (class "Default")
      (node (ref "CN1") (pin "4") (pinfunction "4_4") (pintype "unspecified+no_connect"))
    )
    (net (code "59") (name "unconnected-(CN2-Pad3)") (class "Default")
      (node (ref "CN2") (pin "3") (pinfunction "3_3") (pintype "unspecified+no_connect"))
    )
    (net (code "60") (name "unconnected-(CN2-Pad4)") (class "Default")
      (node (ref "CN2") (pin "4") (pinfunction "4_4") (pintype "unspecified+no_connect"))
    )
    (net (code "61") (name "unconnected-(U5-NRST-Pad37)") (class "Default")
      (node (ref "U5") (pin "37") (pinfunction "NRST_37") (pintype "unspecified+no_connect"))
    )
    (net (code "62") (name "unconnected-(U5-PA4-Pad29)") (class "Default")
      (node (ref "U5") (pin "29") (pinfunction "PA4_29") (pintype "unspecified+no_connect"))
    )
    (net (code "63") (name "unconnected-(U5-PA12-Pad9)") (class "Default")
      (node (ref "U5") (pin "9") (pinfunction "PA12_9") (pintype "unspecified+no_connect"))
    )
    (net (code "64") (name "unconnected-(U5-PB5-Pad13)") (class "Default")
      (node (ref "U5") (pin "13") (pinfunction "PB5_13") (pintype "unspecified+no_connect"))
    )
    (net (code "65") (name "unconnected-(U5-PB6-Pad14)") (class "Default")
      (node (ref "U5") (pin "14") (pinfunction "PB6_14") (pintype "unspecified+no_connect"))
    )
    (net (code "66") (name "unconnected-(U5-PB8-Pad16)") (class "Default")
      (node (ref "U5") (pin "16") (pinfunction "PB8_16") (pintype "unspecified+no_connect"))
    )
    (net (code "67") (name "unconnected-(U5-PB9-Pad17)") (class "Default")
      (node (ref "U5") (pin "17") (pinfunction "PB9_17") (pintype "unspecified+no_connect"))
    )
    (net (code "68") (name "unconnected-(U5-PB11-Pad36)") (class "Default")
      (node (ref "U5") (pin "36") (pinfunction "PB11_36") (pintype "unspecified+no_connect"))
    )
    (net (code "69") (name "unconnected-(U5-PC13-Pad22)") (class "Default")
      (node (ref "U5") (pin "22") (pinfunction "PC13_22") (pintype "unspecified+no_connect"))
    )
    (net (code "70") (name "unconnected-(U5-PC14-Pad23)") (class "Default")
      (node (ref "U5") (pin "23") (pinfunction "PC14_23") (pintype "unspecified+no_connect"))
    )
    (net (code "71") (name "unconnected-(U5-PC15-Pad24)") (class "Default")
      (node (ref "U5") (pin "24") (pinfunction "PC15_24") (pintype "unspecified+no_connect"))
    )
    (net (code "72") (name "unconnected-(U5-VBAT-Pad21)") (class "Default")
      (node (ref "U5") (pin "21") (pinfunction "VBAT_21") (pintype "unspecified+no_connect"))
    )
    (net (code "73") (name "unconnected-(U5-VCC3V3-Pad20)") (class "Default")
      (node (ref "U5") (pin "20") (pinfunction "VCC3V3_20") (pintype "unspecified+no_connect"))
    )
    (net (code "74") (name "unconnected-(U5-VCC3V3-Pad38)") (class "Default")
      (node (ref "U5") (pin "38") (pinfunction "VCC3V3_38") (pintype "unspecified+no_connect"))
    )
  )
)
